# Sheet1.net
KiCad netlist of a schematic drawn in Altium Designer
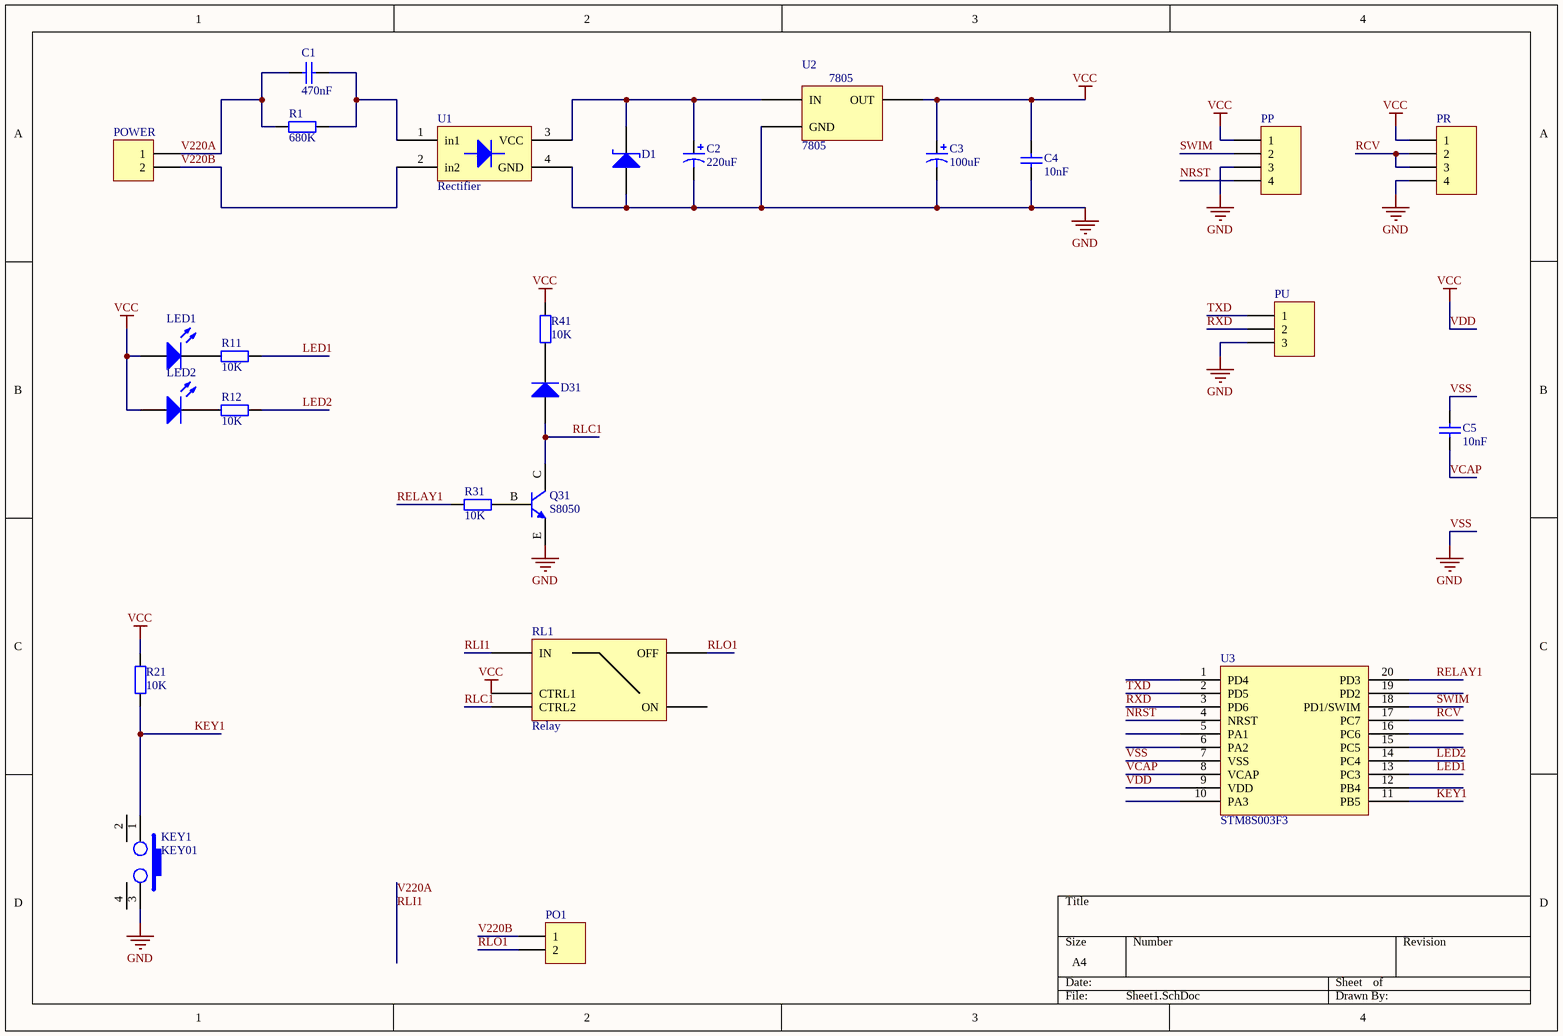
[diagram p0: Sheet1.SchDoc]

(export (version "E")
  (design (tool "Eeschema 10.0.6"))
  (components
    (comp (ref "C1")
      (value "470nF")
      (footprint "Cap3")
      (description "Capacitor")
      (fields (field (name "Comment") "Cap") (field (name "PUBLISHER") "Altium Limited"))
      (libsource (lib "Schlib") (part "Cap"))
    )
    (comp (ref "C2")
      (value "220uF")
      (footprint "CAP1.25")
      (description "Polarized Capacitor (Axial)")
      (fields (field (name "Comment") "Cap Pol2") (field (name "PUBLISHER") "Altium Limited"))
      (libsource (lib "Schlib") (part "Cap Pol2"))
    )
    (comp (ref "C3")
      (value "100uF")
      (footprint "CAP1")
      (description "Polarized Capacitor (Axial)")
      (fields (field (name "Comment") "Cap Pol2") (field (name "PUBLISHER") "Altium Limited"))
      (libsource (lib "Schlib") (part "Cap Pol2"))
    )
    (comp (ref "C4")
      (value "10nF")
      (footprint "0805")
      (description "Capacitor")
      (fields (field (name "Comment") "Cap") (field (name "PUBLISHER") "Altium Limited"))
      (libsource (lib "Schlib") (part "Cap"))
    )
    (comp (ref "C5")
      (value "10nF")
      (footprint "0805")
      (description "Capacitor")
      (fields (field (name "Comment") "Cap") (field (name "PUBLISHER") "Altium Limited"))
      (libsource (lib "Schlib") (part "Cap"))
    )
    (comp (ref "D1")
      (value "Diode_S")
      (footprint "Dinode3")
      (description "Default Diode")
      (fields (field (name "PUBLISHER") "Altium Limited"))
      (libsource (lib "Schlib") (part "Diode_S"))
    )
    (comp (ref "D31")
      (value "Diode")
      (footprint "DINODE")
      (description "Default Diode")
      (fields (field (name "PUBLISHER") "Altium Limited"))
      (libsource (lib "Schlib") (part "Diode"))
    )
    (comp (ref "KEY1") (value "KEY01") (footprint "Key_v") (libsource (lib "Schlib") (part "KEY")))
    (comp (ref "LED1")
      (value "LED1")
      (footprint "LED")
      (description "Typical RED GaAs LED")
      (fields (field (name "PUBLISHER") "Altium Limited"))
      (libsource (lib "Schlib") (part "LED1"))
    )
    (comp (ref "LED2")
      (value "LED1")
      (footprint "LED")
      (description "Typical RED GaAs LED")
      (fields (field (name "PUBLISHER") "Altium Limited"))
      (libsource (lib "Schlib") (part "LED1"))
    )
    (comp (ref "PO1")
      (value "Header 2")
      (footprint "KF301-2P")
      (description "Header, 2-Pin")
      (fields (field (name "PUBLISHER") "Altium Limited"))
      (libsource (lib "") (part "Header 2_1"))
    )
    (comp (ref "POWER")
      (value "Header 2")
      (footprint "KF301-2P")
      (description "Header, 2-Pin")
      (fields (field (name "PUBLISHER") "Altium Limited"))
      (libsource (lib "Schlib") (part "Header 2"))
    )
    (comp (ref "PP")
      (value "Header 4")
      (footprint "HDR1X4")
      (description "Header, 4-Pin")
      (fields (field (name "PUBLISHER") "Altium Limited"))
      (libsource (lib "Schlib") (part "Header 4"))
    )
    (comp (ref "PR")
      (value "Header 4")
      (footprint "HDR1X4")
      (description "Header, 4-Pin")
      (fields (field (name "PUBLISHER") "Altium Limited"))
      (libsource (lib "Schlib") (part "Header 4"))
    )
    (comp (ref "PU")
      (value "Header 3")
      (footprint "HDR1X3")
      (description "Header, 3-Pin")
      (fields (field (name "PUBLISHER") "Altium Limited"))
      (libsource (lib "Schlib") (part "Header 3"))
    )
    (comp (ref "Q31")
      (value "S8050")
      (footprint "SOT23")
      (description "NPN General Purpose Amplifier")
      (fields (field (name "PUBLISHER") "Altium Limited"))
      (libsource (lib "Schlib") (part "S8050"))
    )
    (comp (ref "R1")
      (value "680K")
      (footprint "0805")
      (description "Resistor")
      (fields (field (name "Comment") "Res") (field (name "PUBLISHER") "Altium Limited"))
      (libsource (lib "") (part "Res_2"))
    )
    (comp (ref "R11")
      (value "10K")
      (footprint "0805")
      (description "Resistor")
      (fields (field (name "Comment") "Res") (field (name "PUBLISHER") "Altium Limited"))
      (libsource (lib "") (part "Res_1"))
    )
    (comp (ref "R12")
      (value "10K")
      (footprint "0805")
      (description "Resistor")
      (fields (field (name "Comment") "Res") (field (name "PUBLISHER") "Altium Limited"))
      (libsource (lib "") (part "Res_1"))
    )
    (comp (ref "R21")
      (value "10K")
      (footprint "0805")
      (description "Resistor")
      (fields (field (name "Comment") "Res") (field (name "PUBLISHER") "Altium Limited"))
      (libsource (lib "Schlib") (part "Res"))
    )
    (comp (ref "R31")
      (value "10K")
      (footprint "0805")
      (description "Resistor")
      (fields (field (name "Comment") "Res") (field (name "PUBLISHER") "Altium Limited"))
      (libsource (lib "") (part "Res_1"))
    )
    (comp (ref "R41")
      (value "10K")
      (footprint "0805")
      (description "Resistor")
      (fields (field (name "Comment") "Res") (field (name "PUBLISHER") "Altium Limited"))
      (libsource (lib "Schlib") (part "Res"))
    )
    (comp (ref "RL1") (value "Relay") (footprint "Relay_SRS") (libsource (lib "Schlib") (part "Relay")))
    (comp (ref "U1") (value "Rectifier") (footprint "MB6S") (libsource (lib "Schlib") (part "Rectifier")))
    (comp (ref "U2") (value "7805") (footprint "TO-92A") (libsource (lib "Schlib") (part "7805")))
    (comp (ref "U3") (value "STM8S003F3") (footprint "SSOP20") (libsource (lib "Schlib") (part "STM8S003F3")))
  )
  (nets
    (net (code "1") (name "/KEY1") (class "Default")
      (node (ref "KEY1") (pin "1") (pintype "passive"))
      (node (ref "R21") (pin "1") (pinfunction "1_1") (pintype "passive"))
      (node (ref "U3") (pin "11") (pinfunction "PB5_11") (pintype "passive"))
    )
    (net (code "2") (name "/LED1") (class "Default")
      (node (ref "R11") (pin "1") (pinfunction "1_1") (pintype "passive"))
      (node (ref "U3") (pin "13") (pinfunction "PC3_13") (pintype "passive"))
    )
    (net (code "3") (name "/LED2") (class "Default")
      (node (ref "R12") (pin "1") (pinfunction "1_1") (pintype "passive"))
      (node (ref "U3") (pin "14") (pinfunction "PC4_14") (pintype "passive"))
    )
    (net (code "4") (name "/NRST") (class "Default")
      (node (ref "PP") (pin "4") (pinfunction "4_4") (pintype "passive"))
      (node (ref "U3") (pin "4") (pinfunction "NRST_4") (pintype "passive"))
    )
    (net (code "5") (name "/RCV") (class "Default")
      (node (ref "PR") (pin "2") (pinfunction "2_2") (pintype "passive"))
      (node (ref "PR") (pin "3") (pinfunction "3_3") (pintype "passive"))
      (node (ref "U3") (pin "17") (pinfunction "PC7_17") (pintype "passive"))
    )
    (net (code "6") (name "/RELAY1") (class "Default")
      (node (ref "R31") (pin "2") (pinfunction "2_2") (pintype "passive"))
      (node (ref "U3") (pin "20") (pinfunction "PD3_20") (pintype "passive"))
    )
    (net (code "7") (name "/RLC1") (class "Default")
      (node (ref "D31") (pin "A") (pinfunction "A_A") (pintype "passive"))
      (node (ref "Q31") (pin "C") (pinfunction "C_C") (pintype "passive"))
      (node (ref "RL1") (pin "4") (pinfunction "CTRL2_4") (pintype "passive"))
    )
    (net (code "8") (name "/RLI1") (class "Default")
      (node (ref "C1") (pin "1") (pinfunction "1_1") (pintype "passive"))
      (node (ref "POWER") (pin "1") (pinfunction "1_1") (pintype "passive"))
      (node (ref "R1") (pin "1") (pinfunction "1_1") (pintype "passive"))
      (node (ref "RL1") (pin "5") (pinfunction "IN_5") (pintype "passive"))
    )
    (net (code "9") (name "/RLO1") (class "Default")
      (node (ref "PO1") (pin "2") (pinfunction "2_2") (pintype "passive"))
      (node (ref "RL1") (pin "1") (pinfunction "OFF_1") (pintype "passive"))
    )
    (net (code "10") (name "/RXD") (class "Default")
      (node (ref "PU") (pin "2") (pinfunction "2_2") (pintype "passive"))
      (node (ref "U3") (pin "3") (pinfunction "PD6_3") (pintype "passive"))
    )
    (net (code "11") (name "/SWIM") (class "Default")
      (node (ref "PP") (pin "2") (pinfunction "2_2") (pintype "passive"))
      (node (ref "U3") (pin "18") (pinfunction "PD1/SWIM_18") (pintype "passive"))
    )
    (net (code "12") (name "/TXD") (class "Default")
      (node (ref "PU") (pin "1") (pinfunction "1_1") (pintype "passive"))
      (node (ref "U3") (pin "2") (pinfunction "PD5_2") (pintype "passive"))
    )
    (net (code "13") (name "/V220B") (class "Default")
      (node (ref "PO1") (pin "1") (pinfunction "1_1") (pintype "passive"))
      (node (ref "POWER") (pin "2") (pinfunction "2_2") (pintype "passive"))
      (node (ref "U1") (pin "2") (pinfunction "in2_2") (pintype "passive"))
    )
    (net (code "14") (name "/VCAP") (class "Default")
      (node (ref "C5") (pin "1") (pinfunction "1_1") (pintype "passive"))
      (node (ref "U3") (pin "8") (pinfunction "VCAP_8") (pintype "passive"))
    )
    (net (code "15") (name "GND") (class "Default")
      (node (ref "C2") (pin "2") (pinfunction "2_2") (pintype "passive"))
      (node (ref "C3") (pin "2") (pinfunction "2_2") (pintype "passive"))
      (node (ref "C4") (pin "1") (pinfunction "1_1") (pintype "passive"))
      (node (ref "C5") (pin "2") (pinfunction "2_2") (pintype "passive"))
      (node (ref "D1") (pin "A") (pinfunction "A_A") (pintype "passive"))
      (node (ref "KEY1") (pin "3") (pintype "passive"))
      (node (ref "PP") (pin "3") (pinfunction "3_3") (pintype "passive"))
      (node (ref "PR") (pin "4") (pinfunction "4_4") (pintype "passive"))
      (node (ref "PU") (pin "3") (pinfunction "3_3") (pintype "passive"))
      (node (ref "Q31") (pin "E") (pinfunction "E_E") (pintype "passive"))
      (node (ref "U1") (pin "4") (pinfunction "GND_4") (pintype "passive"))
      (node (ref "U2") (pin "2") (pinfunction "GND_2") (pintype "passive"))
      (node (ref "U3") (pin "7") (pinfunction "VSS_7") (pintype "passive"))
    )
    (net (code "16") (name "Net-(D31-PadK)") (class "Default")
      (node (ref "D31") (pin "K") (pinfunction "K_K") (pintype "passive"))
      (node (ref "R41") (pin "1") (pinfunction "1_1") (pintype "passive"))
    )
    (net (code "17") (name "Net-(LED1-PadK)") (class "Default")
      (node (ref "LED1") (pin "K") (pinfunction "K_K") (pintype "passive"))
      (node (ref "R11") (pin "2") (pinfunction "2_2") (pintype "passive"))
    )
    (net (code "18") (name "Net-(LED2-PadK)") (class "Default")
      (node (ref "LED2") (pin "K") (pinfunction "K_K") (pintype "passive"))
      (node (ref "R12") (pin "2") (pinfunction "2_2") (pintype "passive"))
    )
    (net (code "19") (name "Net-(Q31-PadB)") (class "Default")
      (node (ref "Q31") (pin "B") (pinfunction "B_B") (pintype "passive"))
      (node (ref "R31") (pin "1") (pinfunction "1_1") (pintype "passive"))
    )
    (net (code "20") (name "Net-(U1-VCC)") (class "Default")
      (node (ref "C2") (pin "1") (pinfunction "1_1") (pintype "passive"))
      (node (ref "D1") (pin "K") (pinfunction "K_K") (pintype "passive"))
      (node (ref "U1") (pin "3") (pinfunction "VCC_3") (pintype "passive"))
      (node (ref "U2") (pin "3") (pinfunction "IN_3") (pintype "passive"))
    )
    (net (code "21") (name "Net-(U1-in1)") (class "Default")
      (node (ref "C1") (pin "2") (pinfunction "2_2") (pintype "passive"))
      (node (ref "R1") (pin "2") (pinfunction "2_2") (pintype "passive"))
      (node (ref "U1") (pin "1") (pinfunction "in1_1") (pintype "passive"))
    )
    (net (code "22") (name "VCC") (class "Default")
      (node (ref "C3") (pin "1") (pinfunction "1_1") (pintype "passive"))
      (node (ref "C4") (pin "2") (pinfunction "2_2") (pintype "passive"))
      (node (ref "LED1") (pin "A") (pinfunction "A_A") (pintype "passive"))
      (node (ref "LED2") (pin "A") (pinfunction "A_A") (pintype "passive"))
      (node (ref "PP") (pin "1") (pinfunction "1_1") (pintype "passive"))
      (node (ref "PR") (pin "1") (pinfunction "1_1") (pintype "passive"))
      (node (ref "R21") (pin "2") (pinfunction "2_2") (pintype "passive"))
      (node (ref "R41") (pin "2") (pinfunction "2_2") (pintype "passive"))
      (node (ref "RL1") (pin "3") (pinfunction "CTRL1_3") (pintype "passive"))
      (node (ref "U2") (pin "1") (pinfunction "OUT_1") (pintype "passive"))
      (node (ref "U3") (pin "9") (pinfunction "VDD_9") (pintype "passive"))
    )
    (net (code "23") (name "unconnected-(KEY1-Pad2)") (class "Default")
      (node (ref "KEY1") (pin "2") (pintype "passive"))
    )
    (net (code "24") (name "unconnected-(KEY1-Pad4)") (class "Default")
      (node (ref "KEY1") (pin "4") (pintype "passive"))
    )
    (net (code "25") (name "unconnected-(RL1-ON-Pad2)") (class "Default")
      (node (ref "RL1") (pin "2") (pinfunction "ON_2") (pintype "passive"))
    )
    (net (code "26") (name "unconnected-(U3-PA1-Pad5)") (class "Default")
      (node (ref "U3") (pin "5") (pinfunction "PA1_5") (pintype "passive"))
    )
    (net (code "27") (name "unconnected-(U3-PA2-Pad6)") (class "Default")
      (node (ref "U3") (pin "6") (pinfunction "PA2_6") (pintype "passive"))
    )
    (net (code "28") (name "unconnected-(U3-PA3-Pad10)") (class "Default")
      (node (ref "U3") (pin "10") (pinfunction "PA3_10") (pintype "passive"))
    )
    (net (code "29") (name "unconnected-(U3-PB4-Pad12)") (class "Default")
      (node (ref "U3") (pin "12") (pinfunction "PB4_12") (pintype "passive"))
    )
    (net (code "30") (name "unconnected-(U3-PC5-Pad15)") (class "Default")
      (node (ref "U3") (pin "15") (pinfunction "PC5_15") (pintype "passive"))
    )
    (net (code "31") (name "unconnected-(U3-PC6-Pad16)") (class "Default")
      (node (ref "U3") (pin "16") (pinfunction "PC6_16") (pintype "passive"))
    )
    (net (code "32") (name "unconnected-(U3-PD2-Pad19)") (class "Default")
      (node (ref "U3") (pin "19") (pinfunction "PD2_19") (pintype "passive"))
    )
    (net (code "33") (name "unconnected-(U3-PD4-Pad1)") (class "Default")
      (node (ref "U3") (pin "1") (pinfunction "PD4_1") (pintype "passive"))
    )
  )
)
